# USB_HUB.net
KiCad netlist of a schematic drawn in Altium Designer
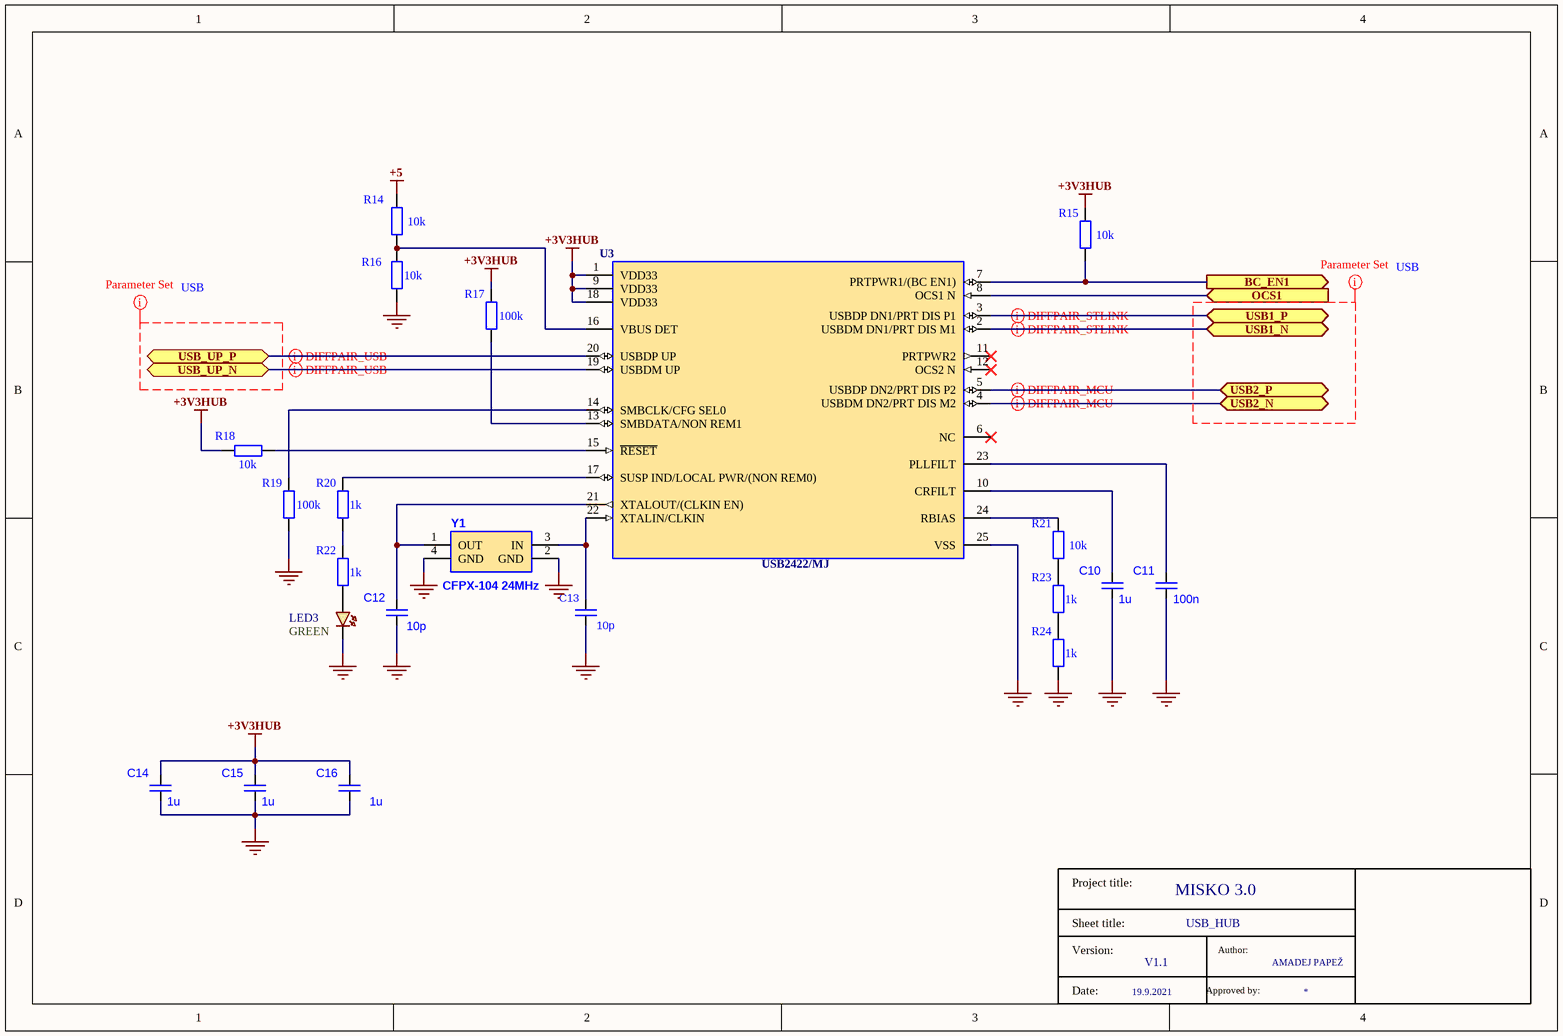
[diagram p0: USB_HUB.SchDoc]

(export (version "E")
  (design (tool "Eeschema 10.0.6"))
  (components
    (comp (ref "C10")
      (value "1u")
      (footprint "C0603")
      (description "Capacitor")
      (libsource (lib "MISKO3_V6") (part "C"))
    )
    (comp (ref "C11")
      (value "100n")
      (footprint "C0603")
      (description "Capacitor")
      (libsource (lib "MISKO3_V6") (part "C"))
    )
    (comp (ref "C12")
      (value "10p")
      (footprint "C0603")
      (description "Capacitor")
      (libsource (lib "MISKO3_V6") (part "C"))
    )
    (comp (ref "C13")
      (value "10p")
      (footprint "C0603")
      (description "Capacitor")
      (libsource (lib "MISKO3_V6") (part "C"))
    )
    (comp (ref "C14")
      (value "1u")
      (footprint "C0603")
      (description "Capacitor")
      (libsource (lib "MISKO3_V6") (part "C"))
    )
    (comp (ref "C15")
      (value "1u")
      (footprint "C0603")
      (description "Capacitor")
      (libsource (lib "MISKO3_V6") (part "C"))
    )
    (comp (ref "C16")
      (value "1u")
      (footprint "C0603")
      (description "Capacitor")
      (libsource (lib "MISKO3_V6") (part "C"))
    )
    (comp (ref "LED3")
      (value "GREEN")
      (footprint "LED0603")
      (description "Green light-emitting diode")
      (libsource (lib "MISKO3_V6") (part "LED"))
    )
    (comp (ref "R14")
      (value "10k")
      (footprint "R1608_0603I_L")
      (description "R")
      (libsource (lib "") (part "R_1"))
    )
    (comp (ref "R15")
      (value "10k")
      (footprint "R1608_0603I_L")
      (description "R")
      (libsource (lib "MISKO3_V6") (part "R"))
    )
    (comp (ref "R16")
      (value "10k")
      (footprint "R1608_0603I_L")
      (description "R")
      (libsource (lib "") (part "R_1"))
    )
    (comp (ref "R17")
      (value "100k")
      (footprint "R1608_0603I_L")
      (description "R")
      (libsource (lib "MISKO3_V6") (part "R"))
    )
    (comp (ref "R18")
      (value "10k")
      (footprint "R1608_0603I_L")
      (description "R")
      (libsource (lib "") (part "R_1"))
    )
    (comp (ref "R19")
      (value "100k")
      (footprint "R1608_0603I_L")
      (description "R")
      (libsource (lib "MISKO3_V6") (part "R"))
    )
    (comp (ref "R20")
      (value "1k")
      (footprint "R1608_0603I_L")
      (description "R")
      (libsource (lib "") (part "R_1"))
    )
    (comp (ref "R21")
      (value "10k")
      (footprint "R1608_0603I_L")
      (description "R")
      (libsource (lib "") (part "R_1"))
    )
    (comp (ref "R22")
      (value "1k")
      (footprint "R1608_0603I_L")
      (description "R")
      (libsource (lib "") (part "R_1"))
    )
    (comp (ref "R23")
      (value "1k")
      (footprint "R1608_0603I_L")
      (description "R")
      (libsource (lib "") (part "R_1"))
    )
    (comp (ref "R24")
      (value "1k")
      (footprint "R1608_0603I_L")
      (description "R")
      (libsource (lib "") (part "R_1"))
    )
    (comp (ref "T4") (value "~") (libsource (lib "MISKO3_V6") (part "Title block")))
    (comp (ref "U3")
      (value "USB2422/MJ")
      (footprint "FP-24-S4QFN-4x4B-0_5P-IPC_C")
      (libsource (lib "MISKO3_V6") (part "USB2422/MJ"))
    )
    (comp (ref "Y1")
      (value "CFPX-104 24MHz")
      (footprint "ABM3B24MHZB2T")
      (libsource (lib "MISKO3_V6") (part "ABM3B-24MHZ-B-2-T"))
    )
  )
  (nets
    (net (code "1") (name "+3V3HUB") (class "Default")
      (node (ref "C14") (pin "2") (pinfunction "2_2") (pintype "passive"))
      (node (ref "C15") (pin "2") (pinfunction "2_2") (pintype "passive"))
      (node (ref "C16") (pin "2") (pinfunction "2_2") (pintype "passive"))
      (node (ref "R15") (pin "2") (pintype "passive"))
      (node (ref "R17") (pin "1") (pintype "passive"))
      (node (ref "R18") (pin "2") (pintype "passive"))
      (node (ref "U3") (pin "1") (pinfunction "VDD33_1") (pintype "power_in"))
      (node (ref "U3") (pin "18") (pinfunction "VDD33_18") (pintype "power_in"))
      (node (ref "U3") (pin "9") (pinfunction "VDD33_9") (pintype "power_in"))
    )
    (net (code "2") (name "+5") (class "Default") (node (ref "R14") (pin "2") (pintype "passive")))
    (net (code "3") (name "/BC_EN1") (class "Default")
      (node (ref "R15") (pin "1") (pintype "passive"))
      (node (ref "U3") (pin "7") (pinfunction "PRTPWR1/(BC_EN1)_7") (pintype "bidirectional"))
    )
    (net (code "4") (name "/OCS1") (class "Default")
      (node (ref "U3") (pin "8") (pinfunction "OCS1_N_8") (pintype "input"))
    )
    (net (code "5") (name "/USB1_N") (class "Default")
      (node (ref "U3") (pin "2") (pinfunction "USBDM_DN1/PRT_DIS_M1_2") (pintype "bidirectional"))
    )
    (net (code "6") (name "/USB1_P") (class "Default")
      (node (ref "U3") (pin "3") (pinfunction "USBDP_DN1/PRT_DIS_P1_3") (pintype "bidirectional"))
    )
    (net (code "7") (name "/USB2_N") (class "Default")
      (node (ref "U3") (pin "4") (pinfunction "USBDM_DN2/PRT_DIS_M2_4") (pintype "bidirectional"))
    )
    (net (code "8") (name "/USB2_P") (class "Default")
      (node (ref "U3") (pin "5") (pinfunction "USBDP_DN2/PRT_DIS_P2_5") (pintype "bidirectional"))
    )
    (net (code "9") (name "/USB_UP_N") (class "Default")
      (node (ref "U3") (pin "19") (pinfunction "USBDM_UP_19") (pintype "bidirectional"))
    )
    (net (code "10") (name "/USB_UP_P") (class "Default")
      (node (ref "U3") (pin "20") (pinfunction "USBDP_UP_20") (pintype "bidirectional"))
    )
    (net (code "11") (name "GND") (class "Default")
      (node (ref "C10") (pin "2") (pinfunction "2_2") (pintype "passive"))
      (node (ref "C11") (pin "2") (pinfunction "2_2") (pintype "passive"))
      (node (ref "C12") (pin "1") (pinfunction "1_1") (pintype "passive"))
      (node (ref "C13") (pin "1") (pinfunction "1_1") (pintype "passive"))
      (node (ref "C14") (pin "1") (pinfunction "1_1") (pintype "passive"))
      (node (ref "C15") (pin "1") (pinfunction "1_1") (pintype "passive"))
      (node (ref "C16") (pin "1") (pinfunction "1_1") (pintype "passive"))
      (node (ref "LED3") (pin "1") (pinfunction "KATODE_1") (pintype "passive"))
      (node (ref "R16") (pin "1") (pintype "passive"))
      (node (ref "R19") (pin "1") (pintype "passive"))
      (node (ref "R24") (pin "1") (pintype "passive"))
      (node (ref "U3") (pin "25") (pinfunction "VSS_25") (pintype "power_in"))
      (node (ref "Y1") (pin "2") (pinfunction "GND_2") (pintype "passive"))
      (node (ref "Y1") (pin "4") (pinfunction "GND_4") (pintype "passive"))
    )
    (net (code "12") (name "Net-(LED3-ANODE)") (class "Default")
      (node (ref "LED3") (pin "2") (pinfunction "ANODE_2") (pintype "passive"))
      (node (ref "R22") (pin "2") (pintype "passive"))
    )
    (net (code "13") (name "Net-(R20-Pad2)") (class "Default")
      (node (ref "R20") (pin "2") (pintype "passive"))
      (node (ref "R22") (pin "1") (pintype "passive"))
    )
    (net (code "14") (name "Net-(R21-Pad2)") (class "Default")
      (node (ref "R21") (pin "2") (pintype "passive"))
      (node (ref "R23") (pin "2") (pintype "passive"))
    )
    (net (code "15") (name "Net-(R23-Pad1)") (class "Default")
      (node (ref "R23") (pin "1") (pintype "passive"))
      (node (ref "R24") (pin "2") (pintype "passive"))
    )
    (net (code "16") (name "Net-(U3-CRFILT)") (class "Default")
      (node (ref "C10") (pin "1") (pinfunction "1_1") (pintype "passive"))
      (node (ref "U3") (pin "10") (pinfunction "CRFILT_10") (pintype "passive"))
    )
    (net (code "17") (name "Net-(U3-PLLFILT)") (class "Default")
      (node (ref "C11") (pin "1") (pinfunction "1_1") (pintype "passive"))
      (node (ref "U3") (pin "23") (pinfunction "PLLFILT_23") (pintype "passive"))
    )
    (net (code "18") (name "Net-(U3-RBIAS)") (class "Default")
      (node (ref "R21") (pin "1") (pintype "passive"))
      (node (ref "U3") (pin "24") (pinfunction "RBIAS_24") (pintype "passive"))
    )
    (net (code "19") (name "Net-(U3-SMBCLK{slash}CFG_SEL0)") (class "Default")
      (node (ref "R19") (pin "2") (pintype "passive"))
      (node (ref "U3") (pin "14") (pinfunction "SMBCLK/CFG_SEL0_14") (pintype "bidirectional"))
    )
    (net (code "20") (name "Net-(U3-SMBDATA{slash}NON_REM1)") (class "Default")
      (node (ref "R17") (pin "2") (pintype "passive"))
      (node (ref "U3") (pin "13") (pinfunction "SMBDATA/NON_REM1_13") (pintype "bidirectional"))
    )
    (net (code "21") (name "Net-(U3-SUSP_IND{slash}LOCAL_PWR{slash}(NON_REM0))") (class "Default")
      (node (ref "R20") (pin "1") (pintype "passive"))
      (node (ref "U3") (pin "17") (pinfunction "SUSP_IND/LOCAL_PWR/(NON_REM0)_17") (pintype "bidirectional"))
    )
    (net (code "22") (name "Net-(U3-VBUS_DET)") (class "Default")
      (node (ref "R14") (pin "1") (pintype "passive"))
      (node (ref "R16") (pin "2") (pintype "passive"))
      (node (ref "U3") (pin "16") (pinfunction "VBUS_DET_16") (pintype "power_in"))
    )
    (net (code "23") (name "Net-(U3-XTALIN{slash}CLKIN)") (class "Default")
      (node (ref "C13") (pin "2") (pinfunction "2_2") (pintype "passive"))
      (node (ref "U3") (pin "22") (pinfunction "XTALIN/CLKIN_22") (pintype "input"))
      (node (ref "Y1") (pin "3") (pinfunction "IN_3") (pintype "passive"))
    )
    (net (code "24") (name "Net-(U3-XTALOUT{slash}(CLKIN_EN))") (class "Default")
      (node (ref "C12") (pin "2") (pinfunction "2_2") (pintype "passive"))
      (node (ref "U3") (pin "21") (pinfunction "XTALOUT/(CLKIN_EN)_21") (pintype "output"))
      (node (ref "Y1") (pin "1") (pinfunction "OUT_1") (pintype "passive"))
    )
    (net (code "25") (name "Net-(U3-~{RESET})") (class "Default")
      (node (ref "R18") (pin "1") (pintype "passive"))
      (node (ref "U3") (pin "15") (pinfunction "~{RESET}_15") (pintype "input"))
    )
    (net (code "26") (name "unconnected-(U3-NC-Pad6)") (class "Default")
      (node (ref "U3") (pin "6") (pinfunction "NC_6") (pintype "passive+no_connect"))
    )
    (net (code "27") (name "unconnected-(U3-OCS2_N-Pad12)") (class "Default")
      (node (ref "U3") (pin "12") (pinfunction "OCS2_N_12") (pintype "input+no_connect"))
    )
    (net (code "28") (name "unconnected-(U3-PRTPWR2-Pad11)") (class "Default")
      (node (ref "U3") (pin "11") (pinfunction "PRTPWR2_11") (pintype "output+no_connect"))
    )
  )
)
